# SCH_DH_7LED.net
KiCad netlist of a schematic drawn in Altium Designer
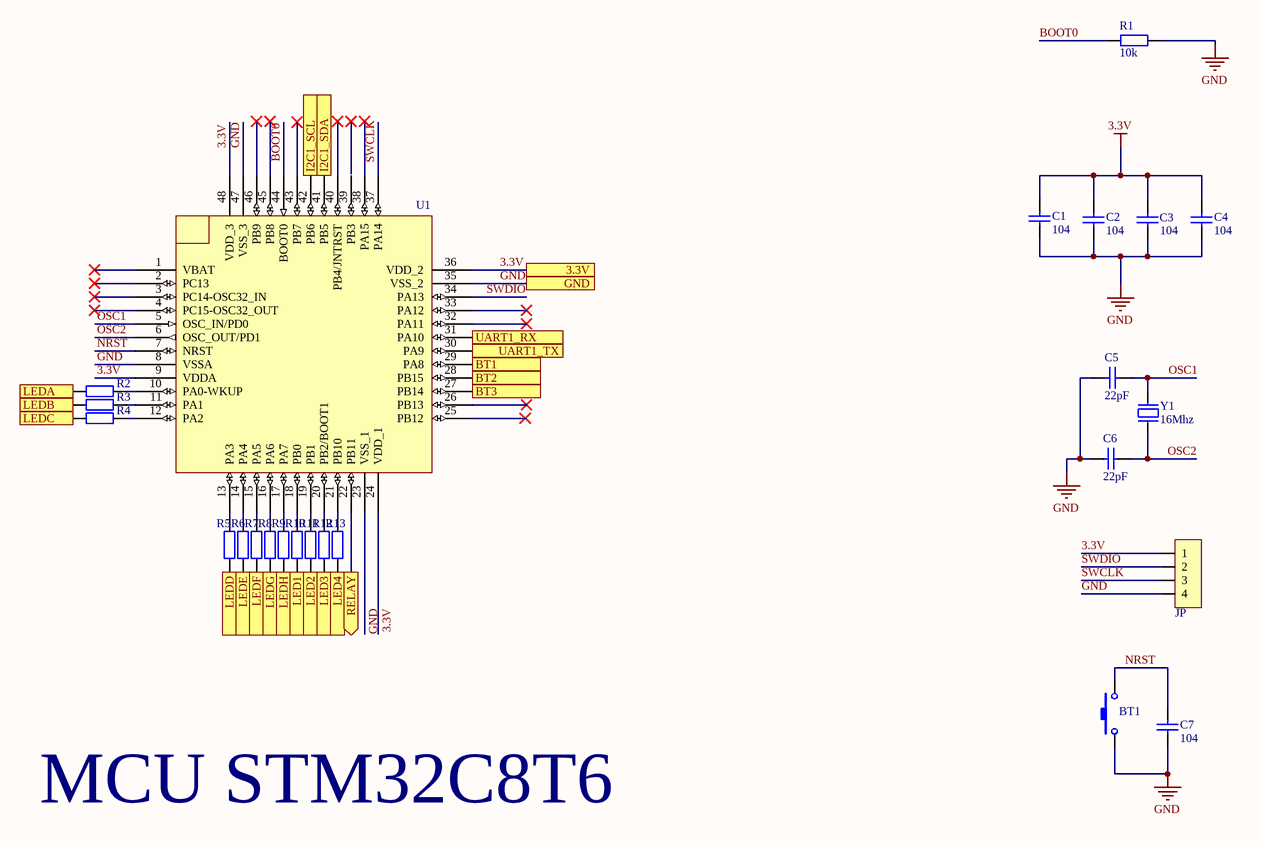
[diagram p0: SCH_DH_7LED.SchDoc]

(export (version "E")
  (design (tool "Eeschema 10.0.6"))
  (components
    (comp (ref "BT1")
      (value "Nut Nhan 2 Chan SMD 3x6x2.5")
      (footprint "Nut Nhan 2 Chan SMD 3x6x2.5")
      (libsource (lib "Altium_Lib_by_KhueNguyenCreator") (part "Nut Nhan 2 Chan SMD 3x6x2.5"))
    )
    (comp (ref "C1")
      (value "104")
      (footprint "tu 0805")
      (description "Dán")
      (libsource (lib "Altium_Lib_by_KhueNguyenCreator") (part "Tu 0805 104 50V 10%"))
    )
    (comp (ref "C2")
      (value "104")
      (footprint "tu 0805")
      (description "Dán")
      (libsource (lib "Altium_Lib_by_KhueNguyenCreator") (part "Tu 0805 104 50V 10%"))
    )
    (comp (ref "C3")
      (value "104")
      (footprint "tu 0805")
      (description "Dán")
      (libsource (lib "Altium_Lib_by_KhueNguyenCreator") (part "Tu 0805 104 50V 10%"))
    )
    (comp (ref "C4")
      (value "104")
      (footprint "tu 0805")
      (description "Dán")
      (libsource (lib "Altium_Lib_by_KhueNguyenCreator") (part "Tu 0805 104 50V 10%"))
    )
    (comp (ref "C5")
      (value "22pF")
      (footprint "tu 0805")
      (description "Dán")
      (libsource (lib "Altium_Lib_by_KhueNguyenCreator") (part "Tu 0805 22pF 50V 10%"))
    )
    (comp (ref "C6")
      (value "22pF")
      (footprint "tu 0805")
      (description "Dán")
      (libsource (lib "Altium_Lib_by_KhueNguyenCreator") (part "Tu 0805 22pF 50V 10%"))
    )
    (comp (ref "C7")
      (value "104")
      (footprint "tu 0805")
      (description "Dán")
      (libsource (lib "Altium_Lib_by_KhueNguyenCreator") (part "Tu 0805 104 50V 10%"))
    )
    (comp (ref "JP1")
      (value "JP")
      (footprint "JP 1x4 DT")
      (description "Cắm")
      (libsource (lib "Altium_Lib_by_KhueNguyenCreator") (part "JP 1x4 2.54 Duc Thang"))
    )
    (comp (ref "R1")
      (value "10k")
      (footprint "tro smd 0805")
      (description "Dán")
      (libsource (lib "Altium_Lib_by_KhueNguyenCreator") (part "Tro 0805 5% 10k"))
    )
    (comp (ref "R2")
      (value "~")
      (footprint "tro smd 0603")
      (description "Dán")
      (libsource (lib "Altium_Lib_by_KhueNguyenCreator") (part "Tro 0603 5% 100R"))
    )
    (comp (ref "R3")
      (value "~")
      (footprint "tro smd 0603")
      (description "Dán")
      (libsource (lib "Altium_Lib_by_KhueNguyenCreator") (part "Tro 0603 5% 100R"))
    )
    (comp (ref "R4")
      (value "~")
      (footprint "tro smd 0603")
      (description "Dán")
      (libsource (lib "Altium_Lib_by_KhueNguyenCreator") (part "Tro 0603 5% 100R"))
    )
    (comp (ref "R5")
      (value "~")
      (footprint "tro smd 0603")
      (description "Dán")
      (libsource (lib "Altium_Lib_by_KhueNguyenCreator") (part "Tro 0603 5% 100R"))
    )
    (comp (ref "R6")
      (value "~")
      (footprint "tro smd 0603")
      (description "Dán")
      (libsource (lib "Altium_Lib_by_KhueNguyenCreator") (part "Tro 0603 5% 100R"))
    )
    (comp (ref "R7")
      (value "~")
      (footprint "tro smd 0603")
      (description "Dán")
      (libsource (lib "Altium_Lib_by_KhueNguyenCreator") (part "Tro 0603 5% 100R"))
    )
    (comp (ref "R8")
      (value "~")
      (footprint "tro smd 0603")
      (description "Dán")
      (libsource (lib "Altium_Lib_by_KhueNguyenCreator") (part "Tro 0603 5% 100R"))
    )
    (comp (ref "R9")
      (value "~")
      (footprint "tro smd 0603")
      (description "Dán")
      (libsource (lib "Altium_Lib_by_KhueNguyenCreator") (part "Tro 0603 5% 100R"))
    )
    (comp (ref "R10")
      (value "~")
      (footprint "tro smd 0603")
      (description "Dán")
      (libsource (lib "Altium_Lib_by_KhueNguyenCreator") (part "Tro 0603 5% 100R"))
    )
    (comp (ref "R11")
      (value "~")
      (footprint "tro smd 0603")
      (description "Dán")
      (libsource (lib "Altium_Lib_by_KhueNguyenCreator") (part "Tro 0603 5% 100R"))
    )
    (comp (ref "R12")
      (value "~")
      (footprint "tro smd 0603")
      (description "Dán")
      (libsource (lib "Altium_Lib_by_KhueNguyenCreator") (part "Tro 0603 5% 100R"))
    )
    (comp (ref "R13")
      (value "~")
      (footprint "tro smd 0603")
      (description "Dán")
      (libsource (lib "Altium_Lib_by_KhueNguyenCreator") (part "Tro 0603 5% 100R"))
    )
    (comp (ref "U1")
      (value "~")
      (footprint "STM32_LQPF48")
      (fields (field (name "PUBLISHER") "Altium Limited"))
      (libsource (lib "Altium_Lib_by_KhueNguyenCreator") (part "STM32F103xx_LQFP48"))
    )
    (comp (ref "Y1")
      (value "16Mhz")
      (footprint "Thach Anh 2 chan SMD")
      (description "Crystal For all Crystal 2pin.")
      (libsource (lib "Altium_Lib_by_KhueNguyenCreator") (part "Thach Anh 2 chan SMD"))
    )
  )
  (nets
    (net (code "1") (name "/BOOT0") (class "Default")
      (node (ref "R1") (pin "2") (pinfunction "2_2") (pintype "passive"))
      (node (ref "U1") (pin "44") (pinfunction "BOOT0_44") (pintype "input"))
    )
    (net (code "2") (name "/BT1") (class "Default")
      (node (ref "U1") (pin "29") (pinfunction "PA8_29") (pintype "bidirectional"))
    )
    (net (code "3") (name "/BT2") (class "Default")
      (node (ref "U1") (pin "28") (pinfunction "PB15_28") (pintype "bidirectional"))
    )
    (net (code "4") (name "/BT3") (class "Default")
      (node (ref "U1") (pin "27") (pinfunction "PB14_27") (pintype "bidirectional"))
    )
    (net (code "5") (name "/I2C1_SCL") (class "Default")
      (node (ref "U1") (pin "42") (pinfunction "PB6_42") (pintype "bidirectional"))
    )
    (net (code "6") (name "/I2C1_SDA") (class "Default")
      (node (ref "U1") (pin "41") (pinfunction "PB5_41") (pintype "bidirectional"))
    )
    (net (code "7") (name "/LED1") (class "Default")
      (node (ref "R10") (pin "1") (pinfunction "1_1") (pintype "passive"))
    )
    (net (code "8") (name "/LED2") (class "Default")
      (node (ref "R11") (pin "1") (pinfunction "1_1") (pintype "passive"))
    )
    (net (code "9") (name "/LED3") (class "Default")
      (node (ref "R12") (pin "1") (pinfunction "1_1") (pintype "passive"))
    )
    (net (code "10") (name "/LED4") (class "Default")
      (node (ref "R13") (pin "1") (pinfunction "1_1") (pintype "passive"))
    )
    (net (code "11") (name "/LEDA") (class "Default")
      (node (ref "R2") (pin "2") (pinfunction "2_2") (pintype "passive"))
    )
    (net (code "12") (name "/LEDB") (class "Default")
      (node (ref "R3") (pin "2") (pinfunction "2_2") (pintype "passive"))
    )
    (net (code "13") (name "/LEDC") (class "Default")
      (node (ref "R4") (pin "2") (pinfunction "2_2") (pintype "passive"))
    )
    (net (code "14") (name "/LEDD") (class "Default")
      (node (ref "R5") (pin "1") (pinfunction "1_1") (pintype "passive"))
    )
    (net (code "15") (name "/LEDE") (class "Default")
      (node (ref "R6") (pin "1") (pinfunction "1_1") (pintype "passive"))
    )
    (net (code "16") (name "/LEDF") (class "Default")
      (node (ref "R7") (pin "1") (pinfunction "1_1") (pintype "passive"))
    )
    (net (code "17") (name "/LEDG") (class "Default")
      (node (ref "R8") (pin "1") (pinfunction "1_1") (pintype "passive"))
    )
    (net (code "18") (name "/LEDH") (class "Default")
      (node (ref "R9") (pin "1") (pinfunction "1_1") (pintype "passive"))
    )
    (net (code "19") (name "/NRST") (class "Default")
      (node (ref "BT1") (pin "2") (pinfunction "2_2") (pintype "passive"))
      (node (ref "C7") (pin "1") (pinfunction "1_1") (pintype "passive"))
      (node (ref "U1") (pin "7") (pinfunction "NRST_7") (pintype "bidirectional"))
    )
    (net (code "20") (name "/OSC1") (class "Default")
      (node (ref "C5") (pin "1") (pinfunction "1_1") (pintype "passive"))
      (node (ref "U1") (pin "5") (pinfunction "OSC_IN/PD0_5") (pintype "input"))
      (node (ref "Y1") (pin "2") (pinfunction "2_2") (pintype "passive"))
    )
    (net (code "21") (name "/OSC2") (class "Default")
      (node (ref "C6") (pin "2") (pinfunction "2_2") (pintype "passive"))
      (node (ref "U1") (pin "6") (pinfunction "OSC_OUT/PD1_6") (pintype "output"))
      (node (ref "Y1") (pin "1") (pinfunction "1_1") (pintype "passive"))
    )
    (net (code "22") (name "/RELAY") (class "Default")
      (node (ref "U1") (pin "22") (pinfunction "PB11_22") (pintype "bidirectional"))
    )
    (net (code "23") (name "/SWCLK") (class "Default")
      (node (ref "JP1") (pin "3") (pinfunction "3_3") (pintype "passive"))
      (node (ref "U1") (pin "37") (pinfunction "PA14_37") (pintype "bidirectional"))
    )
    (net (code "24") (name "/SWDIO") (class "Default")
      (node (ref "JP1") (pin "2") (pinfunction "2_2") (pintype "passive"))
      (node (ref "U1") (pin "34") (pinfunction "PA13_34") (pintype "bidirectional"))
    )
    (net (code "25") (name "/UART1_RX") (class "Default")
      (node (ref "U1") (pin "31") (pinfunction "PA10_31") (pintype "bidirectional"))
    )
    (net (code "26") (name "/UART1_TX") (class "Default")
      (node (ref "U1") (pin "30") (pinfunction "PA9_30") (pintype "bidirectional"))
    )
    (net (code "27") (name "3.3V") (class "Default")
      (node (ref "C1") (pin "1") (pinfunction "1_1") (pintype "passive"))
      (node (ref "C2") (pin "1") (pinfunction "1_1") (pintype "passive"))
      (node (ref "C3") (pin "1") (pinfunction "1_1") (pintype "passive"))
      (node (ref "C4") (pin "1") (pinfunction "1_1") (pintype "passive"))
      (node (ref "JP1") (pin "1") (pinfunction "1_1") (pintype "passive"))
      (node (ref "U1") (pin "24") (pinfunction "VDD_1_24") (pintype "power_in"))
      (node (ref "U1") (pin "36") (pinfunction "VDD_2_36") (pintype "power_in"))
      (node (ref "U1") (pin "48") (pinfunction "VDD_3_48") (pintype "power_in"))
      (node (ref "U1") (pin "9") (pinfunction "VDDA_9") (pintype "power_in"))
    )
    (net (code "28") (name "GND") (class "Default")
      (node (ref "BT1") (pin "1") (pinfunction "1_1") (pintype "passive"))
      (node (ref "C1") (pin "2") (pinfunction "2_2") (pintype "passive"))
      (node (ref "C2") (pin "2") (pinfunction "2_2") (pintype "passive"))
      (node (ref "C3") (pin "2") (pinfunction "2_2") (pintype "passive"))
      (node (ref "C4") (pin "2") (pinfunction "2_2") (pintype "passive"))
      (node (ref "C5") (pin "2") (pinfunction "2_2") (pintype "passive"))
      (node (ref "C6") (pin "1") (pinfunction "1_1") (pintype "passive"))
      (node (ref "C7") (pin "2") (pinfunction "2_2") (pintype "passive"))
      (node (ref "JP1") (pin "4") (pinfunction "4_4") (pintype "passive"))
      (node (ref "R1") (pin "1") (pinfunction "1_1") (pintype "passive"))
      (node (ref "U1") (pin "23") (pinfunction "VSS_1_23") (pintype "power_in"))
      (node (ref "U1") (pin "35") (pinfunction "VSS_2_35") (pintype "power_in"))
      (node (ref "U1") (pin "47") (pinfunction "VSS_3_47") (pintype "power_in"))
      (node (ref "U1") (pin "8") (pinfunction "VSSA_8") (pintype "power_in"))
    )
    (net (code "29") (name "Net-(U1-PA0-WKUP)") (class "Default")
      (node (ref "R2") (pin "1") (pinfunction "1_1") (pintype "passive"))
      (node (ref "U1") (pin "10") (pinfunction "PA0-WKUP_10") (pintype "bidirectional"))
    )
    (net (code "30") (name "Net-(U1-PA1)") (class "Default")
      (node (ref "R3") (pin "1") (pinfunction "1_1") (pintype "passive"))
      (node (ref "U1") (pin "11") (pinfunction "PA1_11") (pintype "bidirectional"))
    )
    (net (code "31") (name "Net-(U1-PA2)") (class "Default")
      (node (ref "R4") (pin "1") (pinfunction "1_1") (pintype "passive"))
      (node (ref "U1") (pin "12") (pinfunction "PA2_12") (pintype "bidirectional"))
    )
    (net (code "32") (name "Net-(U1-PA3)") (class "Default")
      (node (ref "R5") (pin "2") (pinfunction "2_2") (pintype "passive"))
      (node (ref "U1") (pin "13") (pinfunction "PA3_13") (pintype "bidirectional"))
    )
    (net (code "33") (name "Net-(U1-PA4)") (class "Default")
      (node (ref "R6") (pin "2") (pinfunction "2_2") (pintype "passive"))
      (node (ref "U1") (pin "14") (pinfunction "PA4_14") (pintype "bidirectional"))
    )
    (net (code "34") (name "Net-(U1-PA5)") (class "Default")
      (node (ref "R7") (pin "2") (pinfunction "2_2") (pintype "passive"))
      (node (ref "U1") (pin "15") (pinfunction "PA5_15") (pintype "bidirectional"))
    )
    (net (code "35") (name "Net-(U1-PA6)") (class "Default")
      (node (ref "R8") (pin "2") (pinfunction "2_2") (pintype "passive"))
      (node (ref "U1") (pin "16") (pinfunction "PA6_16") (pintype "bidirectional"))
    )
    (net (code "36") (name "Net-(U1-PA7)") (class "Default")
      (node (ref "R9") (pin "2") (pinfunction "2_2") (pintype "passive"))
      (node (ref "U1") (pin "17") (pinfunction "PA7_17") (pintype "bidirectional"))
    )
    (net (code "37") (name "Net-(U1-PB0)") (class "Default")
      (node (ref "R10") (pin "2") (pinfunction "2_2") (pintype "passive"))
      (node (ref "U1") (pin "18") (pinfunction "PB0_18") (pintype "bidirectional"))
    )
    (net (code "38") (name "Net-(U1-PB1)") (class "Default")
      (node (ref "R11") (pin "2") (pinfunction "2_2") (pintype "passive"))
      (node (ref "U1") (pin "19") (pinfunction "PB1_19") (pintype "bidirectional"))
    )
    (net (code "39") (name "Net-(U1-PB2{slash}BOOT1)") (class "Default")
      (node (ref "R12") (pin "2") (pinfunction "2_2") (pintype "passive"))
      (node (ref "U1") (pin "20") (pinfunction "PB2/BOOT1_20") (pintype "bidirectional"))
    )
    (net (code "40") (name "Net-(U1-PB10)") (class "Default")
      (node (ref "R13") (pin "2") (pinfunction "2_2") (pintype "passive"))
      (node (ref "U1") (pin "21") (pinfunction "PB10_21") (pintype "bidirectional"))
    )
    (net (code "41") (name "unconnected-(U1-PA11-Pad32)") (class "Default")
      (node (ref "U1") (pin "32") (pinfunction "PA11_32") (pintype "bidirectional+no_connect"))
    )
    (net (code "42") (name "unconnected-(U1-PA12-Pad33)") (class "Default")
      (node (ref "U1") (pin "33") (pinfunction "PA12_33") (pintype "bidirectional+no_connect"))
    )
    (net (code "43") (name "unconnected-(U1-PA15-Pad38)") (class "Default")
      (node (ref "U1") (pin "38") (pinfunction "PA15_38") (pintype "bidirectional+no_connect"))
    )
    (net (code "44") (name "unconnected-(U1-PB3-Pad39)") (class "Default")
      (node (ref "U1") (pin "39") (pinfunction "PB3_39") (pintype "bidirectional"))
    )
    (net (code "45") (name "unconnected-(U1-PB4{slash}JNTRST-Pad40)") (class "Default")
      (node (ref "U1") (pin "40") (pinfunction "PB4/JNTRST_40") (pintype "bidirectional+no_connect"))
    )
    (net (code "46") (name "unconnected-(U1-PB7-Pad43)") (class "Default")
      (node (ref "U1") (pin "43") (pinfunction "PB7_43") (pintype "bidirectional+no_connect"))
    )
    (net (code "47") (name "unconnected-(U1-PB8-Pad45)") (class "Default")
      (node (ref "U1") (pin "45") (pinfunction "PB8_45") (pintype "bidirectional+no_connect"))
    )
    (net (code "48") (name "unconnected-(U1-PB9-Pad46)") (class "Default")
      (node (ref "U1") (pin "46") (pinfunction "PB9_46") (pintype "bidirectional+no_connect"))
    )
    (net (code "49") (name "unconnected-(U1-PB12-Pad25)") (class "Default")
      (node (ref "U1") (pin "25") (pinfunction "PB12_25") (pintype "bidirectional"))
    )
    (net (code "50") (name "unconnected-(U1-PB13-Pad26)") (class "Default")
      (node (ref "U1") (pin "26") (pinfunction "PB13_26") (pintype "bidirectional+no_connect"))
    )
    (net (code "51") (name "unconnected-(U1-PC13-Pad2)") (class "Default")
      (node (ref "U1") (pin "2") (pinfunction "PC13_2") (pintype "bidirectional+no_connect"))
    )
    (net (code "52") (name "unconnected-(U1-PC14-OSC32_IN-Pad3)") (class "Default")
      (node (ref "U1") (pin "3") (pinfunction "PC14-OSC32_IN_3") (pintype "bidirectional+no_connect"))
    )
    (net (code "53") (name "unconnected-(U1-PC15-OSC32_OUT-Pad4)") (class "Default")
      (node (ref "U1") (pin "4") (pinfunction "PC15-OSC32_OUT_4") (pintype "bidirectional+no_connect"))
    )
    (net (code "54") (name "unconnected-(U1-VBAT-Pad1)") (class "Default")
      (node (ref "U1") (pin "1") (pinfunction "VBAT_1") (pintype "power_in+no_connect"))
    )
  )
)
